# 11-5.net
KiCad netlist of a schematic drawn in EAGLE
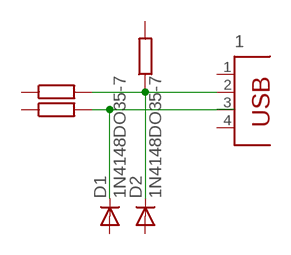
[diagram p0: schematic, sheet 1]

(export (version "E")
  (design (tool "Eeschema 10.0.6"))
  (components
    (comp (ref "1")
      (value "PN61729")
      (footprint "eagle-import:PN61729")
      (libsource (lib "eagle-import") (part "PN61729"))
    )
    (comp (ref "D1")
      (value "1N4148DO35-7")
      (footprint "eagle-import:DO35-7")
      (libsource (lib "eagle-import") (part "1N4148DO35-7"))
    )
    (comp (ref "D2")
      (value "1N4148DO35-7")
      (footprint "eagle-import:DO35-7")
      (libsource (lib "eagle-import") (part "1N4148DO35-7"))
    )
  )
  (nets
    (net (code "1") (name "Net-(1-Pad2)") (class "Default")
      (node (ref "1") (pin "2") (pinfunction "2_2") (pintype "passive"))
      (node (ref "D2") (pin "C") (pinfunction "C_C") (pintype "passive"))
    )
    (net (code "2") (name "Net-(1-Pad3)") (class "Default")
      (node (ref "1") (pin "3") (pinfunction "3_3") (pintype "passive"))
      (node (ref "D1") (pin "C") (pinfunction "C_C") (pintype "passive"))
    )
    (net (code "3") (name "unconnected-(1-Pad1)") (class "Default")
      (node (ref "1") (pin "1") (pinfunction "1_1") (pintype "passive"))
    )
    (net (code "4") (name "unconnected-(1-Pad4)") (class "Default")
      (node (ref "1") (pin "4") (pinfunction "4_4") (pintype "passive"))
    )
    (net (code "5") (name "unconnected-(D1-PadA)") (class "Default")
      (node (ref "D1") (pin "A") (pinfunction "A_A") (pintype "passive"))
    )
    (net (code "6") (name "unconnected-(D2-PadA)") (class "Default")
      (node (ref "D2") (pin "A") (pinfunction "A_A") (pintype "passive"))
    )
  )
)
